# MCU.net
KiCad netlist of a schematic drawn in Altium Designer
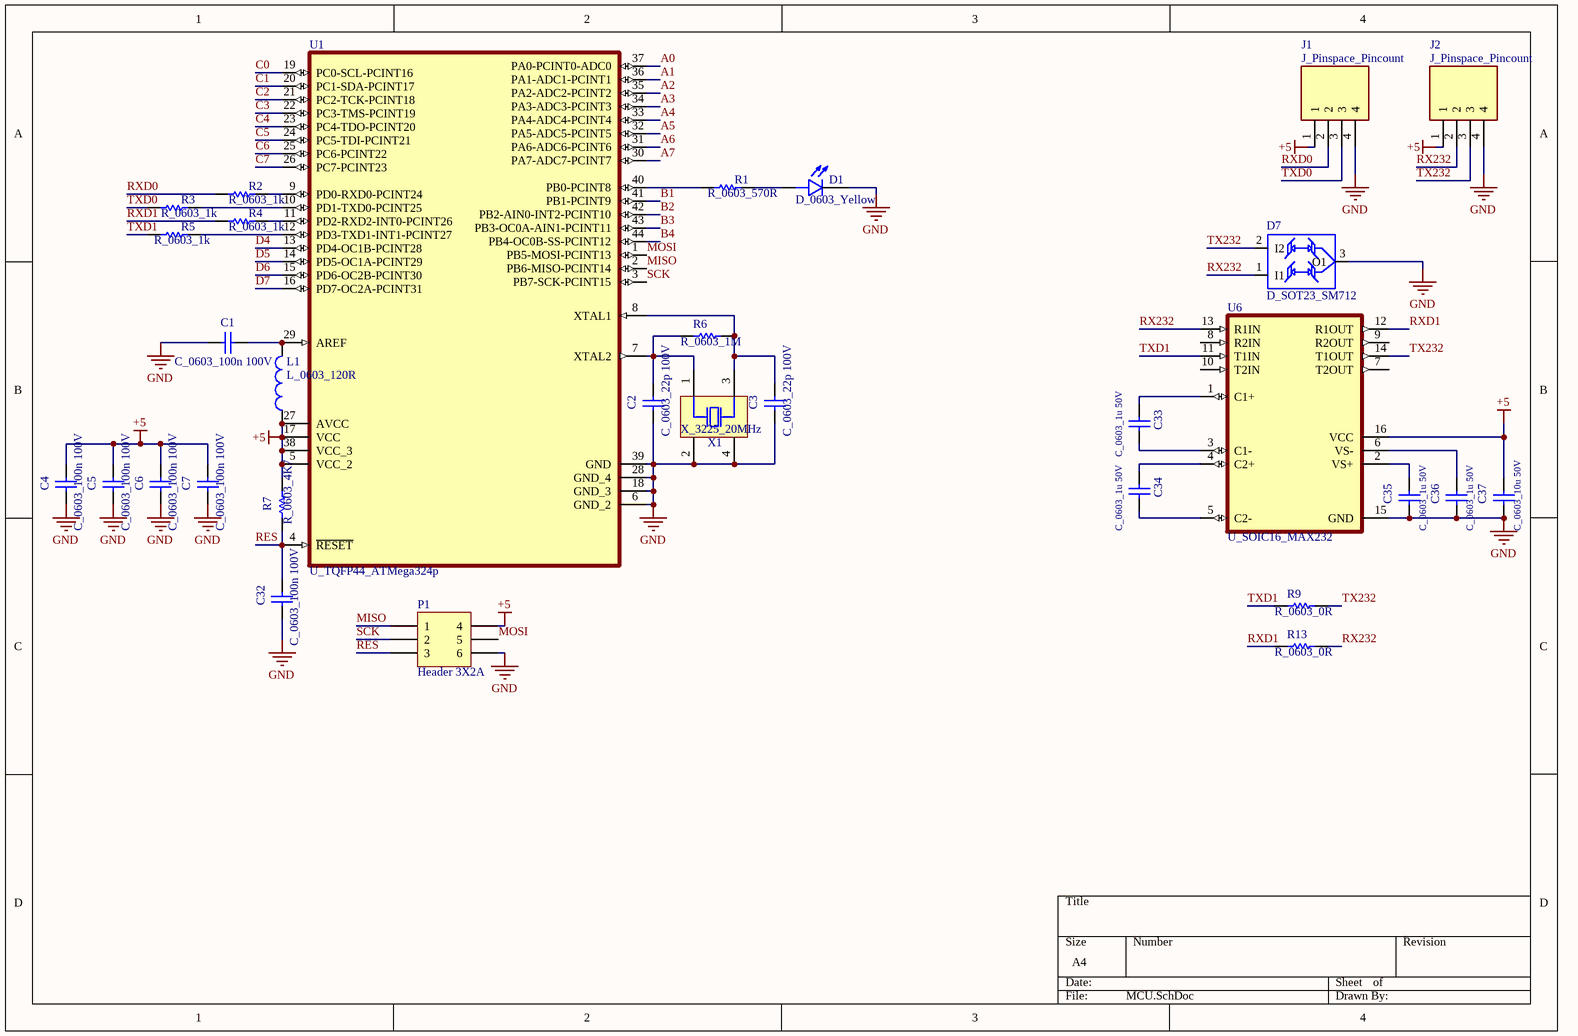
[diagram p0: MCU.SchDoc]

(export (version "E")
  (design (tool "Eeschema 10.0.6"))
  (components
    (comp (ref "C1")
      (value "C_0603_100n 100V")
      (footprint "CAP 0603")
      (description "Capacitor")
      (fields (field (name "PUBLISHER") "Altium Limited"))
      (libsource (lib "HUE") (part "Cap"))
    )
    (comp (ref "C2")
      (value "C_0603_22p 100V")
      (footprint "CAP 0603")
      (description "Capacitor")
      (fields (field (name "PUBLISHER") "Altium Limited"))
      (libsource (lib "HUE") (part "Cap"))
    )
    (comp (ref "C3")
      (value "C_0603_22p 100V")
      (footprint "CAP 0603")
      (description "Capacitor")
      (fields (field (name "PUBLISHER") "Altium Limited"))
      (libsource (lib "HUE") (part "Cap"))
    )
    (comp (ref "C4")
      (value "C_0603_100n 100V")
      (footprint "CAP 0603")
      (description "Capacitor")
      (fields (field (name "PUBLISHER") "Altium Limited"))
      (libsource (lib "HUE") (part "Cap"))
    )
    (comp (ref "C5")
      (value "C_0603_100n 100V")
      (footprint "CAP 0603")
      (description "Capacitor")
      (fields (field (name "PUBLISHER") "Altium Limited"))
      (libsource (lib "HUE") (part "Cap"))
    )
    (comp (ref "C6")
      (value "C_0603_100n 100V")
      (footprint "CAP 0603")
      (description "Capacitor")
      (fields (field (name "PUBLISHER") "Altium Limited"))
      (libsource (lib "HUE") (part "Cap"))
    )
    (comp (ref "C7")
      (value "C_0603_100n 100V")
      (footprint "CAP 0603")
      (description "Capacitor")
      (fields (field (name "PUBLISHER") "Altium Limited"))
      (libsource (lib "HUE") (part "Cap"))
    )
    (comp (ref "C32")
      (value "C_0603_100n 100V")
      (footprint "CAP 0603")
      (description "Capacitor")
      (fields (field (name "PUBLISHER") "Altium Limited"))
      (libsource (lib "HUE") (part "Cap"))
    )
    (comp (ref "C33")
      (value "C_0603_1u 50V")
      (footprint "CAP 0603")
      (description "Capacitor")
      (fields (field (name "PUBLISHER") "Altium Limited"))
      (libsource (lib "HUE") (part "Cap"))
    )
    (comp (ref "C34")
      (value "C_0603_1u 50V")
      (footprint "CAP 0603")
      (description "Capacitor")
      (fields (field (name "PUBLISHER") "Altium Limited"))
      (libsource (lib "HUE") (part "Cap"))
    )
    (comp (ref "C35")
      (value "C_0603_1u 50V")
      (footprint "CAP 0603")
      (description "Capacitor")
      (fields (field (name "PUBLISHER") "Altium Limited"))
      (libsource (lib "HUE") (part "Cap"))
    )
    (comp (ref "C36")
      (value "C_0603_1u 50V")
      (footprint "CAP 0603")
      (description "Capacitor")
      (fields (field (name "PUBLISHER") "Altium Limited"))
      (libsource (lib "HUE") (part "Cap"))
    )
    (comp (ref "C37")
      (value "C_0603_10u 50V")
      (footprint "CAP 0603")
      (description "Capacitor")
      (fields (field (name "PUBLISHER") "Altium Limited"))
      (libsource (lib "HUE") (part "Cap"))
    )
    (comp (ref "D1")
      (value "D_0603_Yellow")
      (footprint "Led 0603")
      (description "Led")
      (fields (field (name "MP") "SML-D12FWT86") (field (name "MF") "Rohm"))
      (libsource (lib "HUE") (part "Led"))
    )
    (comp (ref "D7")
      (value "D_SOT23_SM712")
      (footprint "SOT23")
      (description "TVS Diode Array")
      (fields (field (name "MP") "SM712") (field (name "MF") "Semtech"))
      (libsource (lib "HUE") (part "DIODE TVS ARRAY"))
    )
    (comp (ref "J1")
      (value "J_Pinspace_Pincount")
      (footprint "4 Pin PCB STB 5.08")
      (fields (field (name "MP") "TBP02R1-381-04BE"))
      (libsource (lib "HUE") (part "4 Pin PCB Terminal Block"))
    )
    (comp (ref "J2")
      (value "J_Pinspace_Pincount")
      (footprint "4 Pin PCB STB 5.08")
      (fields (field (name "MP") "TBP02R1-381-04BE"))
      (libsource (lib "HUE") (part "4 Pin PCB Terminal Block"))
    )
    (comp (ref "L1")
      (value "L_0603_120R")
      (footprint "Inductor 0603")
      (description "Inductor")
      (fields (field (name "PUBLISHER") "Altium Limited"))
      (libsource (lib "HUE") (part "Inductor"))
    )
    (comp (ref "P1")
      (value "Header 3X2A")
      (footprint "HDR2X3_CEN")
      (description "Header, 3-Pin, Dual row")
      (fields (field (name "PUBLISHER") "Altium Limited"))
      (libsource (lib "Miscellaneous Connectors") (part "Header 3X2A"))
    )
    (comp (ref "R1")
      (value "R_0603_570R")
      (footprint "RES 0603")
      (description "Resistor")
      (fields (field (name "PUBLISHER") "Altium Limited"))
      (libsource (lib "HUE") (part "Res"))
    )
    (comp (ref "R2")
      (value "R_0603_1k")
      (footprint "RES 0603")
      (description "Resistor")
      (fields (field (name "PUBLISHER") "Altium Limited"))
      (libsource (lib "HUE") (part "Res"))
    )
    (comp (ref "R3")
      (value "R_0603_1k")
      (footprint "RES 0603")
      (description "Resistor")
      (fields (field (name "PUBLISHER") "Altium Limited"))
      (libsource (lib "HUE") (part "Res"))
    )
    (comp (ref "R4")
      (value "R_0603_1k")
      (footprint "RES 0603")
      (description "Resistor")
      (fields (field (name "PUBLISHER") "Altium Limited"))
      (libsource (lib "HUE") (part "Res"))
    )
    (comp (ref "R5")
      (value "R_0603_1k")
      (footprint "RES 0603")
      (description "Resistor")
      (fields (field (name "PUBLISHER") "Altium Limited"))
      (libsource (lib "HUE") (part "Res"))
    )
    (comp (ref "R6")
      (value "R_0603_1M")
      (footprint "RES 0603")
      (description "Resistor")
      (fields (field (name "PUBLISHER") "Altium Limited"))
      (libsource (lib "HUE") (part "Res"))
    )
    (comp (ref "R7")
      (value "R_0603_4K7")
      (footprint "RES 0603")
      (description "Resistor")
      (fields (field (name "PUBLISHER") "Altium Limited"))
      (libsource (lib "HUE") (part "Res"))
    )
    (comp (ref "R9")
      (value "R_0603_0R")
      (footprint "RES 0603")
      (description "Resistor")
      (fields (field (name "PUBLISHER") "Altium Limited"))
      (libsource (lib "HUE") (part "Res"))
    )
    (comp (ref "R13")
      (value "R_0603_0R")
      (footprint "RES 0603")
      (description "Resistor")
      (fields (field (name "PUBLISHER") "Altium Limited"))
      (libsource (lib "HUE") (part "Res"))
    )
    (comp (ref "U1")
      (value "U_TQFP44_ATMega324p")
      (footprint "TQFP44")
      (description "AVR AVRÂ® ATmega Microcontroller IC 8-Bit 20MHz 32KB _16K x 16_ FLASH 44-TQFP _10x10_")
      (fields (field (name "MF") "Microchip") (field (name "MP") "ATMEGA324P-20AU"))
      (libsource (lib "HUE") (part "ATMEGA324P-20AU"))
    )
    (comp (ref "U6")
      (value "U_SOIC16_MAX232")
      (footprint "SOIC16")
      (description "Dual EIA-232 driver and receiver 16-SOIC 0 to 70")
      (fields (field (name "MF") "Texas Instruments") (field (name "MP") "MAX232DW"))
      (libsource (lib "HUE") (part "MAX232DW"))
    )
    (comp (ref "X1")
      (value "X_3225_20MHz")
      (footprint "Crystal 3.2x2.5")
      (description "Crystal 4 Pin")
      (libsource (lib "HUE") (part "Crystal 4 Pin"))
    )
  )
  (nets
    (net (code "1") (name "+5") (class "Default")
      (node (ref "C37") (pin "2") (pinfunction "2_2") (pintype "passive"))
      (node (ref "C4") (pin "2") (pinfunction "2_2") (pintype "passive"))
      (node (ref "C5") (pin "2") (pinfunction "2_2") (pintype "passive"))
      (node (ref "C6") (pin "2") (pinfunction "2_2") (pintype "passive"))
      (node (ref "C7") (pin "2") (pinfunction "2_2") (pintype "passive"))
      (node (ref "J1") (pin "1") (pinfunction "1_1") (pintype "passive"))
      (node (ref "J2") (pin "1") (pinfunction "1_1") (pintype "passive"))
      (node (ref "L1") (pin "1") (pinfunction "1_1") (pintype "passive"))
      (node (ref "P1") (pin "4") (pinfunction "4_4") (pintype "passive"))
      (node (ref "R7") (pin "2") (pinfunction "2_2") (pintype "passive"))
      (node (ref "U1") (pin "17") (pinfunction "VCC_17") (pintype "power_in"))
      (node (ref "U1") (pin "27") (pinfunction "AVCC_27") (pintype "power_in"))
      (node (ref "U1") (pin "38") (pinfunction "VCC_3_38") (pintype "power_in"))
      (node (ref "U1") (pin "5") (pinfunction "VCC_2_5") (pintype "power_in"))
      (node (ref "U6") (pin "16") (pinfunction "VCC_16") (pintype "power_in"))
    )
    (net (code "2") (name "/A0") (class "Default")
      (node (ref "U1") (pin "37") (pinfunction "PA0-PCINT0-ADC0_37") (pintype "bidirectional"))
    )
    (net (code "3") (name "/A1") (class "Default")
      (node (ref "U1") (pin "36") (pinfunction "PA1-ADC1-PCINT1_36") (pintype "bidirectional"))
    )
    (net (code "4") (name "/A2") (class "Default")
      (node (ref "U1") (pin "35") (pinfunction "PA2-ADC2-PCINT2_35") (pintype "bidirectional"))
    )
    (net (code "5") (name "/A3") (class "Default")
      (node (ref "U1") (pin "34") (pinfunction "PA3-ADC3-PCINT3_34") (pintype "bidirectional"))
    )
    (net (code "6") (name "/A4") (class "Default")
      (node (ref "U1") (pin "33") (pinfunction "PA4-ADC4-PCINT4_33") (pintype "bidirectional"))
    )
    (net (code "7") (name "/A5") (class "Default")
      (node (ref "U1") (pin "32") (pinfunction "PA5-ADC5-PCINT5_32") (pintype "bidirectional"))
    )
    (net (code "8") (name "/A6") (class "Default")
      (node (ref "U1") (pin "31") (pinfunction "PA6-ADC6-PCINT6_31") (pintype "bidirectional"))
    )
    (net (code "9") (name "/A7") (class "Default")
      (node (ref "U1") (pin "30") (pinfunction "PA7-ADC7-PCINT7_30") (pintype "bidirectional"))
    )
    (net (code "10") (name "/B1") (class "Default")
      (node (ref "U1") (pin "41") (pinfunction "PB1-PCINT9_41") (pintype "bidirectional"))
    )
    (net (code "11") (name "/B2") (class "Default")
      (node (ref "U1") (pin "42") (pinfunction "PB2-AIN0-INT2-PCINT10_42") (pintype "bidirectional"))
    )
    (net (code "12") (name "/B3") (class "Default")
      (node (ref "U1") (pin "43") (pinfunction "PB3-OC0A-AIN1-PCINT11_43") (pintype "bidirectional"))
    )
    (net (code "13") (name "/B4") (class "Default")
      (node (ref "U1") (pin "44") (pinfunction "PB4-OC0B-SS-PCINT12_44") (pintype "bidirectional"))
    )
    (net (code "14") (name "/C0") (class "Default")
      (node (ref "U1") (pin "19") (pinfunction "PC0-SCL-PCINT16_19") (pintype "bidirectional"))
    )
    (net (code "15") (name "/C1") (class "Default")
      (node (ref "U1") (pin "20") (pinfunction "PC1-SDA-PCINT17_20") (pintype "bidirectional"))
    )
    (net (code "16") (name "/C2") (class "Default")
      (node (ref "U1") (pin "21") (pinfunction "PC2-TCK-PCINT18_21") (pintype "bidirectional"))
    )
    (net (code "17") (name "/C3") (class "Default")
      (node (ref "U1") (pin "22") (pinfunction "PC3-TMS-PCINT19_22") (pintype "bidirectional"))
    )
    (net (code "18") (name "/C4") (class "Default")
      (node (ref "U1") (pin "23") (pinfunction "PC4-TDO-PCINT20_23") (pintype "bidirectional"))
    )
    (net (code "19") (name "/C5") (class "Default")
      (node (ref "U1") (pin "24") (pinfunction "PC5-TDI-PCINT21_24") (pintype "bidirectional"))
    )
    (net (code "20") (name "/C6") (class "Default")
      (node (ref "U1") (pin "25") (pinfunction "PC6-PCINT22_25") (pintype "bidirectional"))
    )
    (net (code "21") (name "/C7") (class "Default")
      (node (ref "U1") (pin "26") (pinfunction "PC7-PCINT23_26") (pintype "bidirectional"))
    )
    (net (code "22") (name "/D4") (class "Default")
      (node (ref "U1") (pin "13") (pinfunction "PD4-OC1B-PCINT28_13") (pintype "bidirectional"))
    )
    (net (code "23") (name "/D5") (class "Default")
      (node (ref "U1") (pin "14") (pinfunction "PD5-OC1A-PCINT29_14") (pintype "bidirectional"))
    )
    (net (code "24") (name "/D6") (class "Default")
      (node (ref "U1") (pin "15") (pinfunction "PD6-OC2B-PCINT30_15") (pintype "bidirectional"))
    )
    (net (code "25") (name "/D7") (class "Default")
      (node (ref "U1") (pin "16") (pinfunction "PD7-OC2A-PCINT31_16") (pintype "bidirectional"))
    )
    (net (code "26") (name "/MISO") (class "Default")
      (node (ref "P1") (pin "1") (pinfunction "1_1") (pintype "passive"))
      (node (ref "U1") (pin "2") (pinfunction "PB6-MISO-PCINT14_2") (pintype "bidirectional"))
    )
    (net (code "27") (name "/MOSI") (class "Default")
      (node (ref "P1") (pin "5") (pinfunction "5_5") (pintype "passive"))
      (node (ref "U1") (pin "1") (pinfunction "PB5-MOSI-PCINT13_1") (pintype "bidirectional"))
    )
    (net (code "28") (name "/RES") (class "Default")
      (node (ref "C32") (pin "2") (pinfunction "2_2") (pintype "passive"))
      (node (ref "P1") (pin "3") (pinfunction "3_3") (pintype "passive"))
      (node (ref "R7") (pin "1") (pinfunction "1_1") (pintype "passive"))
      (node (ref "U1") (pin "4") (pinfunction "~{RESET}_4") (pintype "input"))
    )
    (net (code "29") (name "/RX232") (class "Default")
      (node (ref "D7") (pin "1") (pinfunction "I1_1") (pintype "passive"))
      (node (ref "J2") (pin "2") (pinfunction "2_2") (pintype "passive"))
      (node (ref "R13") (pin "2") (pinfunction "2_2") (pintype "passive"))
      (node (ref "U6") (pin "13") (pinfunction "R1IN_13") (pintype "input"))
    )
    (net (code "30") (name "/RXD0") (class "Default")
      (node (ref "J1") (pin "2") (pinfunction "2_2") (pintype "passive"))
      (node (ref "R2") (pin "2") (pinfunction "2_2") (pintype "passive"))
    )
    (net (code "31") (name "/RXD1") (class "Default")
      (node (ref "R13") (pin "1") (pinfunction "1_1") (pintype "passive"))
      (node (ref "R4") (pin "2") (pinfunction "2_2") (pintype "passive"))
      (node (ref "U6") (pin "12") (pinfunction "R1OUT_12") (pintype "output"))
    )
    (net (code "32") (name "/SCK") (class "Default")
      (node (ref "P1") (pin "2") (pinfunction "2_2") (pintype "passive"))
      (node (ref "U1") (pin "3") (pinfunction "PB7-SCK-PCINT15_3") (pintype "bidirectional"))
    )
    (net (code "33") (name "/TX232") (class "Default")
      (node (ref "D7") (pin "2") (pinfunction "I2_2") (pintype "passive"))
      (node (ref "J2") (pin "3") (pinfunction "3_3") (pintype "passive"))
      (node (ref "R9") (pin "2") (pinfunction "2_2") (pintype "passive"))
      (node (ref "U6") (pin "14") (pinfunction "T1OUT_14") (pintype "output"))
    )
    (net (code "34") (name "/TXD0") (class "Default")
      (node (ref "J1") (pin "3") (pinfunction "3_3") (pintype "passive"))
      (node (ref "R3") (pin "2") (pinfunction "2_2") (pintype "passive"))
    )
    (net (code "35") (name "/TXD1") (class "Default")
      (node (ref "R5") (pin "2") (pinfunction "2_2") (pintype "passive"))
      (node (ref "R9") (pin "1") (pinfunction "1_1") (pintype "passive"))
      (node (ref "U6") (pin "11") (pinfunction "T1IN_11") (pintype "input"))
    )
    (net (code "36") (name "GND") (class "Default")
      (node (ref "C1") (pin "1") (pinfunction "1_1") (pintype "passive"))
      (node (ref "C2") (pin "2") (pinfunction "2_2") (pintype "passive"))
      (node (ref "C3") (pin "2") (pinfunction "2_2") (pintype "passive"))
      (node (ref "C32") (pin "1") (pinfunction "1_1") (pintype "passive"))
      (node (ref "C35") (pin "1") (pinfunction "1_1") (pintype "passive"))
      (node (ref "C36") (pin "1") (pinfunction "1_1") (pintype "passive"))
      (node (ref "C37") (pin "1") (pinfunction "1_1") (pintype "passive"))
      (node (ref "C4") (pin "1") (pinfunction "1_1") (pintype "passive"))
      (node (ref "C5") (pin "1") (pinfunction "1_1") (pintype "passive"))
      (node (ref "C6") (pin "1") (pinfunction "1_1") (pintype "passive"))
      (node (ref "C7") (pin "1") (pinfunction "1_1") (pintype "passive"))
      (node (ref "D1") (pin "2") (pinfunction "C_2") (pintype "passive"))
      (node (ref "D7") (pin "3") (pinfunction "O1_3") (pintype "passive"))
      (node (ref "J1") (pin "4") (pinfunction "4_4") (pintype "passive"))
      (node (ref "J2") (pin "4") (pinfunction "4_4") (pintype "passive"))
      (node (ref "P1") (pin "6") (pinfunction "6_6") (pintype "passive"))
      (node (ref "U1") (pin "18") (pinfunction "GND_3_18") (pintype "passive"))
      (node (ref "U1") (pin "28") (pinfunction "GND_4_28") (pintype "passive"))
      (node (ref "U1") (pin "39") (pinfunction "GND_39") (pintype "passive"))
      (node (ref "U1") (pin "6") (pinfunction "GND_2_6") (pintype "passive"))
      (node (ref "U6") (pin "15") (pinfunction "GND_15") (pintype "power_in"))
      (node (ref "X1") (pin "2") (pinfunction "NC_2") (pintype "passive"))
      (node (ref "X1") (pin "4") (pinfunction "NC_4") (pintype "passive"))
    )
    (net (code "37") (name "Net-(D1-A)") (class "Default")
      (node (ref "D1") (pin "1") (pinfunction "A_1") (pintype "passive"))
      (node (ref "R1") (pin "1") (pinfunction "1_1") (pintype "passive"))
    )
    (net (code "38") (name "Net-(U1-AREF)") (class "Default")
      (node (ref "C1") (pin "2") (pinfunction "2_2") (pintype "passive"))
      (node (ref "L1") (pin "2") (pinfunction "2_2") (pintype "passive"))
      (node (ref "U1") (pin "29") (pinfunction "AREF_29") (pintype "input"))
    )
    (net (code "39") (name "Net-(U1-PB0-PCINT8)") (class "Default")
      (node (ref "R1") (pin "2") (pinfunction "2_2") (pintype "passive"))
      (node (ref "U1") (pin "40") (pinfunction "PB0-PCINT8_40") (pintype "bidirectional"))
    )
    (net (code "40") (name "Net-(U1-PD0-RXD0-PCINT24)") (class "Default")
      (node (ref "R2") (pin "1") (pinfunction "1_1") (pintype "passive"))
      (node (ref "U1") (pin "9") (pinfunction "PD0-RXD0-PCINT24_9") (pintype "bidirectional"))
    )
    (net (code "41") (name "Net-(U1-PD1-TXD0-PCINT25)") (class "Default")
      (node (ref "R3") (pin "1") (pinfunction "1_1") (pintype "passive"))
      (node (ref "U1") (pin "10") (pinfunction "PD1-TXD0-PCINT25_10") (pintype "bidirectional"))
    )
    (net (code "42") (name "Net-(U1-PD2-RXD2-INT0-PCINT26)") (class "Default")
      (node (ref "R4") (pin "1") (pinfunction "1_1") (pintype "passive"))
      (node (ref "U1") (pin "11") (pinfunction "PD2-RXD2-INT0-PCINT26_11") (pintype "bidirectional"))
    )
    (net (code "43") (name "Net-(U1-PD3-TXD1-INT1-PCINT27)") (class "Default")
      (node (ref "R5") (pin "1") (pinfunction "1_1") (pintype "passive"))
      (node (ref "U1") (pin "12") (pinfunction "PD3-TXD1-INT1-PCINT27_12") (pintype "bidirectional"))
    )
    (net (code "44") (name "Net-(U1-XTAL1)") (class "Default")
      (node (ref "C3") (pin "1") (pinfunction "1_1") (pintype "passive"))
      (node (ref "R6") (pin "2") (pinfunction "2_2") (pintype "passive"))
      (node (ref "U1") (pin "8") (pinfunction "XTAL1_8") (pintype "input"))
      (node (ref "X1") (pin "3") (pinfunction "OSC2_3") (pintype "passive"))
    )
    (net (code "45") (name "Net-(U1-XTAL2)") (class "Default")
      (node (ref "C2") (pin "1") (pinfunction "1_1") (pintype "passive"))
      (node (ref "R6") (pin "1") (pinfunction "1_1") (pintype "passive"))
      (node (ref "U1") (pin "7") (pinfunction "XTAL2_7") (pintype "output"))
      (node (ref "X1") (pin "1") (pinfunction "OSC1_1") (pintype "passive"))
    )
    (net (code "46") (name "Net-(U6-C1+)") (class "Default")
      (node (ref "C33") (pin "1") (pinfunction "1_1") (pintype "passive"))
      (node (ref "U6") (pin "1") (pinfunction "C1+_1") (pintype "bidirectional"))
    )
    (net (code "47") (name "Net-(U6-C1-)") (class "Default")
      (node (ref "C33") (pin "2") (pinfunction "2_2") (pintype "passive"))
      (node (ref "U6") (pin "3") (pinfunction "C1-_3") (pintype "bidirectional"))
    )
    (net (code "48") (name "Net-(U6-C2+)") (class "Default")
      (node (ref "C34") (pin "1") (pinfunction "1_1") (pintype "passive"))
      (node (ref "U6") (pin "4") (pinfunction "C2+_4") (pintype "bidirectional"))
    )
    (net (code "49") (name "Net-(U6-C2-)") (class "Default")
      (node (ref "C34") (pin "2") (pinfunction "2_2") (pintype "passive"))
      (node (ref "U6") (pin "5") (pinfunction "C2-_5") (pintype "bidirectional"))
    )
    (net (code "50") (name "Net-(U6-VS+)") (class "Default")
      (node (ref "C35") (pin "2") (pinfunction "2_2") (pintype "passive"))
      (node (ref "U6") (pin "2") (pinfunction "VS+_2") (pintype "power_in"))
    )
    (net (code "51") (name "Net-(U6-VS-)") (class "Default")
      (node (ref "C36") (pin "2") (pinfunction "2_2") (pintype "passive"))
      (node (ref "U6") (pin "6") (pinfunction "VS-_6") (pintype "power_in"))
    )
    (net (code "52") (name "unconnected-(U6-R2IN-Pad8)") (class "Default")
      (node (ref "U6") (pin "8") (pinfunction "R2IN_8") (pintype "input"))
    )
    (net (code "53") (name "unconnected-(U6-R2OUT-Pad9)") (class "Default")
      (node (ref "U6") (pin "9") (pinfunction "R2OUT_9") (pintype "output"))
    )
    (net (code "54") (name "unconnected-(U6-T2IN-Pad10)") (class "Default")
      (node (ref "U6") (pin "10") (pinfunction "T2IN_10") (pintype "input"))
    )
    (net (code "55") (name "unconnected-(U6-T2OUT-Pad7)") (class "Default")
      (node (ref "U6") (pin "7") (pinfunction "T2OUT_7") (pintype "output"))
    )
  )
)
